# MCU.net
KiCad netlist of a schematic drawn in Altium Designer
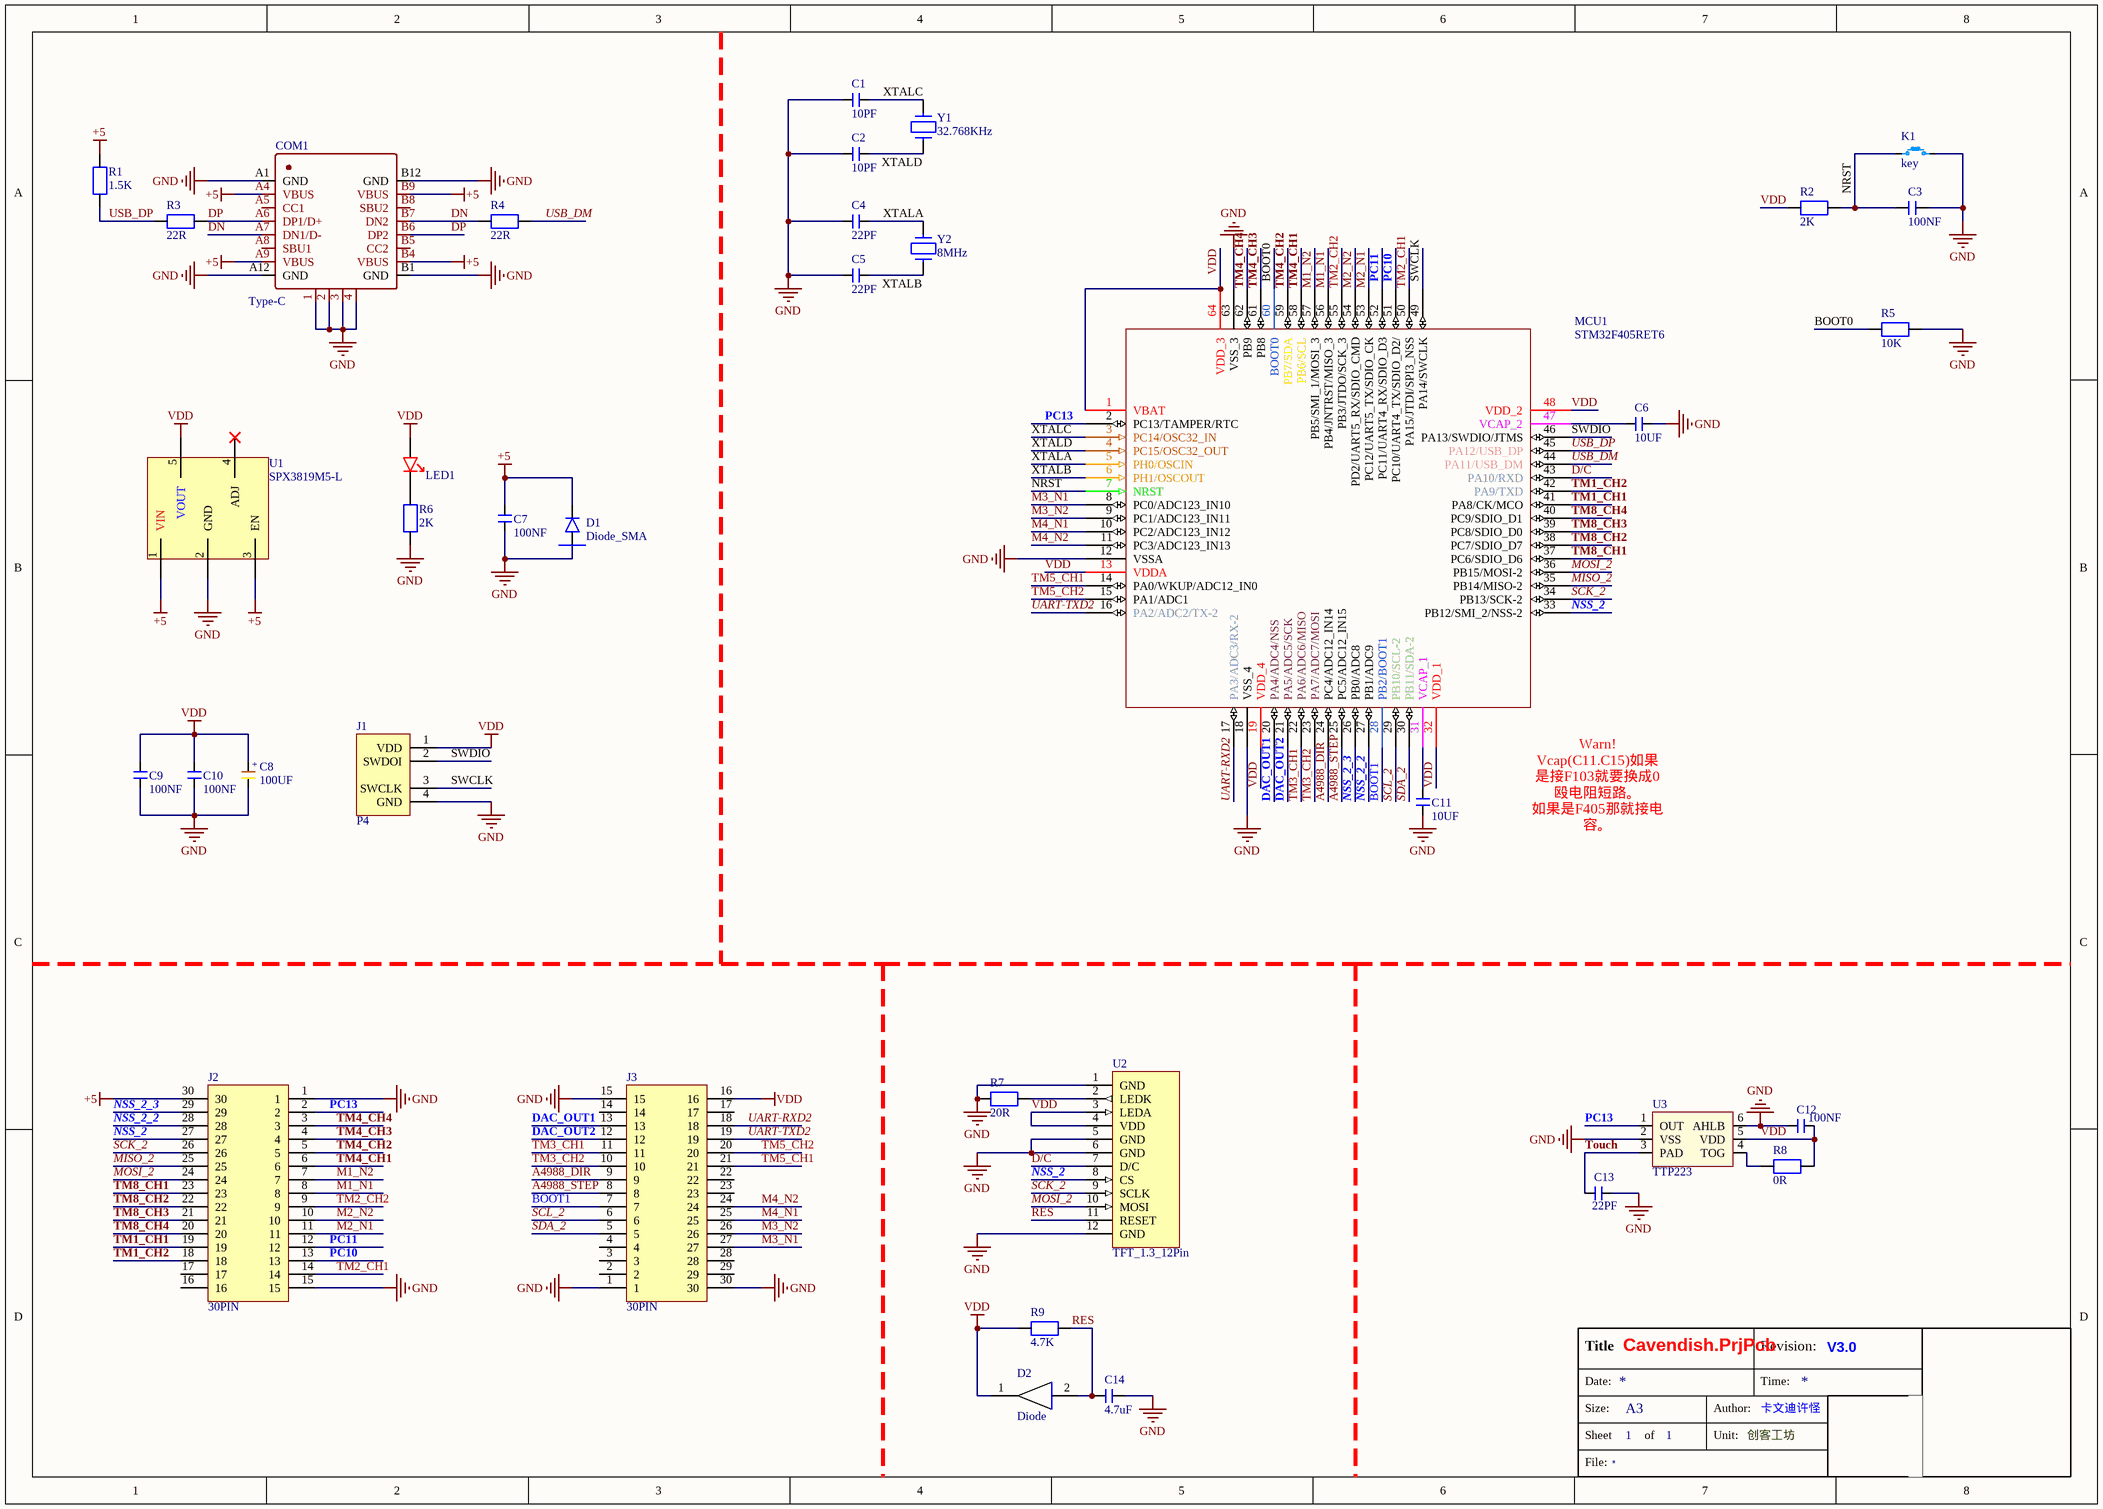
[diagram p0: MCU.SchDoc]

(export (version "E")
  (design (tool "Eeschema 10.0.6"))
  (components
    (comp (ref "C1")
      (value "10PF")
      (footprint "CAP_0603")
      (description "CAP  12~50V")
      (libsource (lib "User") (part "CAP"))
    )
    (comp (ref "C2")
      (value "10PF")
      (footprint "CAP_0603")
      (description "CAP  12~50V")
      (libsource (lib "User") (part "CAP"))
    )
    (comp (ref "C3")
      (value "100NF")
      (footprint "CAP_0603")
      (description "CAP")
      (libsource (lib "Schlib1") (part "CAP_SDM"))
    )
    (comp (ref "C4")
      (value "22PF")
      (footprint "CAP_0603")
      (description "CAP  12~50V")
      (libsource (lib "User") (part "CAP"))
    )
    (comp (ref "C5")
      (value "22PF")
      (footprint "CAP_0603")
      (description "CAP  12~50V")
      (libsource (lib "User") (part "CAP"))
    )
    (comp (ref "C6")
      (value "10UF")
      (footprint "CAP_0603")
      (description "CAP  12~50V")
      (libsource (lib "User") (part "CAP"))
    )
    (comp (ref "C7")
      (value "100NF")
      (footprint "CAP_0603")
      (description "CAP  12~50V")
      (libsource (lib "User") (part "CAP"))
    )
    (comp (ref "C8")
      (value "100UF")
      (footprint "CAP_3528_B")
      (description "CAP  6~12V  钽电容")
      (libsource (lib "User") (part "CAP_TA"))
    )
    (comp (ref "C9")
      (value "100NF")
      (footprint "CAP_0603")
      (description "CAP  12~50V")
      (libsource (lib "User") (part "CAP"))
    )
    (comp (ref "C10")
      (value "100NF")
      (footprint "CAP_0603")
      (description "CAP  12~50V")
      (libsource (lib "User") (part "CAP"))
    )
    (comp (ref "C11")
      (value "10UF")
      (footprint "CAP_0603")
      (description "CAP  12~50V")
      (libsource (lib "User") (part "CAP"))
    )
    (comp (ref "C12")
      (value "100NF")
      (footprint "CAP_0603")
      (description "CAP  12~50V")
      (libsource (lib "User") (part "CAP"))
    )
    (comp (ref "C13")
      (value "22PF")
      (footprint "CAP_0603")
      (description "CAP  12~50V")
      (libsource (lib "User") (part "CAP"))
    )
    (comp (ref "C14")
      (value "4.7uF")
      (footprint "CAP_0603")
      (description "CAP")
      (libsource (lib "Schlib1") (part "CAP_SDM"))
    )
    (comp (ref "COM1")
      (value "Type-C")
      (footprint "USB-tYPE_C_C")
      (description "USB")
      (libsource (lib "User") (part "USB-type_c"))
    )
    (comp (ref "D1")
      (value "Diode_SMA")
      (footprint "DIODE_SOD123")
      (description "Diode_肖特基")
      (libsource (lib "User") (part "Diode-SM"))
    )
    (comp (ref "D2")
      (value "Diode")
      (footprint "SOD123")
      (description "开关二极管")
      (libsource (lib "Schlib1") (part "Diode-SOD"))
    )
    (comp (ref "J1") (value "P4") (footprint "XH2.54-WS-4P") (libsource (lib "User") (part "SWD")))
    (comp (ref "J2")
      (value "30PIN")
      (footprint "BTB_Double_30Pin_Up")
      (libsource (lib "") (part "BTB_DOUBLE_30PIN_1"))
    )
    (comp (ref "J3")
      (value "30PIN")
      (footprint "BTB_Double_30Pin_Up")
      (libsource (lib "User") (part "BTB_DOUBLE_30PIN"))
    )
    (comp (ref "K1")
      (value "key")
      (footprint "KEY-A")
      (description "Key")
      (libsource (lib "Schlib1") (part "key"))
    )
    (comp (ref "LED1")
      (value "LED_R/G/B/Y")
      (footprint "LED_0603_R")
      (description "LED")
      (libsource (lib "User") (part "LED"))
    )
    (comp (ref "MCU1")
      (value "STM32F405RET6")
      (footprint "LQFP_64_10X10")
      (description "MCU")
      (libsource (lib "User") (part "STM32f4_R"))
    )
    (comp (ref "R1")
      (value "1.5K")
      (footprint "RESC_0603_2")
      (description "RES 贴片")
      (libsource (lib "User") (part "RES_S"))
    )
    (comp (ref "R2")
      (value "2K")
      (footprint "RESC_0603_2")
      (description "RES 贴片")
      (libsource (lib "User") (part "RES_S"))
    )
    (comp (ref "R3")
      (value "22R")
      (footprint "RESC_0603_2")
      (description "RES 贴片")
      (libsource (lib "User") (part "RES_S"))
    )
    (comp (ref "R4")
      (value "22R")
      (footprint "RESC_0603_2")
      (description "RES 贴片")
      (libsource (lib "User") (part "RES_S"))
    )
    (comp (ref "R5")
      (value "10K")
      (footprint "RESC_0603_2")
      (description "RES 贴片")
      (libsource (lib "User") (part "RES_S"))
    )
    (comp (ref "R6")
      (value "2K")
      (footprint "RESC_0603_2")
      (description "RES 贴片")
      (libsource (lib "User") (part "RES_S"))
    )
    (comp (ref "R7")
      (value "20R")
      (footprint "RESC_0603_2")
      (description "RES 贴片")
      (libsource (lib "User") (part "RES_S"))
    )
    (comp (ref "R8")
      (value "0R")
      (footprint "RESC_0603_2")
      (description "RES 贴片")
      (libsource (lib "User") (part "RES_S"))
    )
    (comp (ref "R9")
      (value "4.7K")
      (footprint "RESC_0603_2")
      (description "RES 贴片")
      (libsource (lib "User") (part "RES_S"))
    )
    (comp (ref "U1")
      (value "SPX3819M5-L")
      (footprint "SOT23_5")
      (description "DC-DC   3.3V  500ma")
      (libsource (lib "Schlib1") (part "SPX3819M5-L"))
    )
    (comp (ref "U2")
      (value "TFT_1.3_12Pin")
      (footprint "LCD_1.3B")
      (description "ST7789V-SPI")
      (libsource (lib "User") (part "LCD_1.3   T"))
    )
    (comp (ref "U3")
      (value "TTP223")
      (footprint "SOT-23-6")
      (description "触摸芯片")
      (libsource (lib "User") (part "TTP223"))
    )
    (comp (ref "Y1")
      (value "32.768KHz")
      (footprint "XTAL_SMD_3215")
      (description "CRYSTAL")
      (libsource (lib "Schlib1") (part "XTAL"))
    )
    (comp (ref "Y2")
      (value "8MHz")
      (footprint "XTAL_3225")
      (description "CRYSTAL")
      (libsource (lib "Schlib1") (part "XTAL"))
    )
  )
  (nets
    (net (code "1") (name "+5") (class "Default")
      (node (ref "C7") (pin "2") (pinfunction "0_2") (pintype "passive"))
      (node (ref "COM1") (pin "A4") (pinfunction "VBUS_A4") (pintype "passive"))
      (node (ref "COM1") (pin "A9") (pinfunction "VBUS_A9") (pintype "passive"))
      (node (ref "COM1") (pin "B4") (pinfunction "VBUS_B4") (pintype "passive"))
      (node (ref "COM1") (pin "B9") (pinfunction "VBUS_B9") (pintype "passive"))
      (node (ref "D1") (pin "2") (pinfunction "N_2") (pintype "passive"))
      (node (ref "J2") (pin "30") (pinfunction "30_30") (pintype "passive"))
      (node (ref "R1") (pin "1") (pinfunction "1_1") (pintype "passive"))
      (node (ref "U1") (pin "1") (pinfunction "VIN_1") (pintype "passive"))
      (node (ref "U1") (pin "3") (pinfunction "EN_3") (pintype "passive"))
    )
    (net (code "2") (name "/A4988_DIR") (class "Default")
      (node (ref "J3") (pin "9") (pinfunction "9_9") (pintype "passive"))
      (node (ref "MCU1") (pin "24") (pinfunction "PC4/ADC12_IN14_24") (pintype "bidirectional"))
    )
    (net (code "3") (name "/A4988_STEP") (class "Default")
      (node (ref "J3") (pin "8") (pinfunction "8_8") (pintype "passive"))
      (node (ref "MCU1") (pin "25") (pinfunction "PC5/ADC12_IN15_25") (pintype "bidirectional"))
    )
    (net (code "4") (name "/BOOT0") (class "Default")
      (node (ref "MCU1") (pin "60") (pinfunction "BOOT0_60") (pintype "passive"))
      (node (ref "R5") (pin "1") (pinfunction "1_1") (pintype "passive"))
    )
    (net (code "5") (name "/BOOT1") (class "Default")
      (node (ref "J3") (pin "7") (pinfunction "7_7") (pintype "passive"))
      (node (ref "MCU1") (pin "28") (pinfunction "PB2/BOOT1_28") (pintype "passive"))
    )
    (net (code "6") (name "/DAC_OUT1") (class "Default")
      (node (ref "J3") (pin "13") (pinfunction "13_13") (pintype "passive"))
      (node (ref "MCU1") (pin "20") (pinfunction "PA4/ADC4/NSS_20") (pintype "bidirectional"))
    )
    (net (code "7") (name "/DAC_OUT2") (class "Default")
      (node (ref "J3") (pin "12") (pinfunction "12_12") (pintype "passive"))
      (node (ref "MCU1") (pin "21") (pinfunction "PA5/ADC5/SCK_21") (pintype "bidirectional"))
    )
    (net (code "8") (name "/DN") (class "Default")
      (node (ref "COM1") (pin "A7") (pinfunction "DN1/D-_A7") (pintype "passive"))
      (node (ref "COM1") (pin "B7") (pinfunction "DN2_B7") (pintype "passive"))
      (node (ref "R4") (pin "1") (pinfunction "1_1") (pintype "passive"))
    )
    (net (code "9") (name "/DP") (class "Default")
      (node (ref "COM1") (pin "A6") (pinfunction "DP1/D+_A6") (pintype "passive"))
      (node (ref "COM1") (pin "B6") (pinfunction "DP2_B6") (pintype "passive"))
      (node (ref "R3") (pin "1") (pinfunction "1_1") (pintype "passive"))
    )
    (net (code "10") (name "/D{slash}C") (class "Default")
      (node (ref "MCU1") (pin "43") (pinfunction "PA10/RXD_43") (pintype "bidirectional"))
      (node (ref "U2") (pin "7") (pinfunction "D/C_7") (pintype "passive"))
    )
    (net (code "11") (name "/M1_N1") (class "Default")
      (node (ref "J2") (pin "8") (pinfunction "8_8") (pintype "passive"))
      (node (ref "MCU1") (pin "56") (pinfunction "PB4/JNTRST/MISO_3_56") (pintype "bidirectional"))
    )
    (net (code "12") (name "/M1_N2") (class "Default")
      (node (ref "J2") (pin "7") (pinfunction "7_7") (pintype "passive"))
      (node (ref "MCU1") (pin "57") (pinfunction "PB5/SMI_1/MOSI_3_57") (pintype "bidirectional"))
    )
    (net (code "13") (name "/M2_N1") (class "Default")
      (node (ref "J2") (pin "11") (pinfunction "11_11") (pintype "passive"))
      (node (ref "MCU1") (pin "53") (pinfunction "PC12/UART5_TX/SDIO_CK_53") (pintype "bidirectional"))
    )
    (net (code "14") (name "/M2_N2") (class "Default")
      (node (ref "J2") (pin "10") (pinfunction "10_10") (pintype "passive"))
      (node (ref "MCU1") (pin "54") (pinfunction "PD2/UART5_RX/SDIO_CMD_54") (pintype "bidirectional"))
    )
    (net (code "15") (name "/M3_N1") (class "Default")
      (node (ref "J3") (pin "27") (pinfunction "27_27") (pintype "passive"))
      (node (ref "MCU1") (pin "8") (pinfunction "PC0/ADC123_IN10_8") (pintype "bidirectional"))
    )
    (net (code "16") (name "/M3_N2") (class "Default")
      (node (ref "J3") (pin "26") (pinfunction "26_26") (pintype "passive"))
      (node (ref "MCU1") (pin "9") (pinfunction "PC1/ADC123_IN11_9") (pintype "bidirectional"))
    )
    (net (code "17") (name "/M4_N1") (class "Default")
      (node (ref "J3") (pin "25") (pinfunction "25_25") (pintype "passive"))
      (node (ref "MCU1") (pin "10") (pinfunction "PC2/ADC123_IN12_10") (pintype "bidirectional"))
    )
    (net (code "18") (name "/M4_N2") (class "Default")
      (node (ref "J3") (pin "24") (pinfunction "24_24") (pintype "passive"))
      (node (ref "MCU1") (pin "11") (pinfunction "PC3/ADC123_IN13_11") (pintype "bidirectional"))
    )
    (net (code "19") (name "/MISO_2") (class "Default")
      (node (ref "J2") (pin "25") (pinfunction "25_25") (pintype "passive"))
      (node (ref "MCU1") (pin "35") (pinfunction "PB14/MISO-2_35") (pintype "bidirectional"))
    )
    (net (code "20") (name "/MOSI_2") (class "Default")
      (node (ref "J2") (pin "24") (pinfunction "24_24") (pintype "passive"))
      (node (ref "MCU1") (pin "36") (pinfunction "PB15/MOSI-2_36") (pintype "bidirectional"))
      (node (ref "U2") (pin "10") (pinfunction "MOSI_10") (pintype "input"))
    )
    (net (code "21") (name "/NRST") (class "Default")
      (node (ref "C3") (pin "2") (pinfunction "0_2") (pintype "passive"))
      (node (ref "K1") (pin "2") (pintype "passive"))
      (node (ref "MCU1") (pin "7") (pinfunction "NRST_7") (pintype "input"))
      (node (ref "R2") (pin "2") (pinfunction "2_2") (pintype "passive"))
    )
    (net (code "22") (name "/NSS_2") (class "Default")
      (node (ref "J2") (pin "27") (pinfunction "27_27") (pintype "passive"))
      (node (ref "MCU1") (pin "33") (pinfunction "PB12/SMI_2/NSS-2_33") (pintype "bidirectional"))
      (node (ref "U2") (pin "8") (pinfunction "CS_8") (pintype "input"))
    )
    (net (code "23") (name "/NSS_2_2") (class "Default")
      (node (ref "J2") (pin "28") (pinfunction "28_28") (pintype "passive"))
      (node (ref "MCU1") (pin "27") (pinfunction "PB1/ADC9_27") (pintype "bidirectional"))
    )
    (net (code "24") (name "/NSS_2_3") (class "Default")
      (node (ref "J2") (pin "29") (pinfunction "29_29") (pintype "passive"))
      (node (ref "MCU1") (pin "26") (pinfunction "PB0/ADC8_26") (pintype "bidirectional"))
    )
    (net (code "25") (name "/PC10") (class "Default")
      (node (ref "J2") (pin "13") (pinfunction "13_13") (pintype "passive"))
      (node (ref "MCU1") (pin "51") (pinfunction "PC10/UART4_TX/SDIO_D2/_51") (pintype "bidirectional"))
    )
    (net (code "26") (name "/PC11") (class "Default")
      (node (ref "J2") (pin "12") (pinfunction "12_12") (pintype "passive"))
      (node (ref "MCU1") (pin "52") (pinfunction "PC11/UART4_RX/SDIO_D3_52") (pintype "bidirectional"))
    )
    (net (code "27") (name "/PC13") (class "Default")
      (node (ref "J2") (pin "2") (pinfunction "2_2") (pintype "passive"))
      (node (ref "MCU1") (pin "2") (pinfunction "PC13/TAMPER/RTC_2") (pintype "bidirectional"))
      (node (ref "U3") (pin "1") (pinfunction "OUT_1") (pintype "passive"))
    )
    (net (code "28") (name "/RES") (class "Default")
      (node (ref "C14") (pin "2") (pinfunction "0_2") (pintype "passive"))
      (node (ref "D2") (pin "2") (pinfunction "P_2") (pintype "passive"))
      (node (ref "R9") (pin "2") (pinfunction "2_2") (pintype "passive"))
      (node (ref "U2") (pin "11") (pinfunction "RESET_11") (pintype "passive"))
    )
    (net (code "29") (name "/SCK_2") (class "Default")
      (node (ref "J2") (pin "26") (pinfunction "26_26") (pintype "passive"))
      (node (ref "MCU1") (pin "34") (pinfunction "PB13/SCK-2_34") (pintype "bidirectional"))
      (node (ref "U2") (pin "9") (pinfunction "SCLK_9") (pintype "input"))
    )
    (net (code "30") (name "/SCL_2") (class "Default")
      (node (ref "J3") (pin "6") (pinfunction "6_6") (pintype "passive"))
      (node (ref "MCU1") (pin "29") (pinfunction "PB10/SCL-2_29") (pintype "bidirectional"))
    )
    (net (code "31") (name "/SDA_2") (class "Default")
      (node (ref "J3") (pin "5") (pinfunction "5_5") (pintype "passive"))
      (node (ref "MCU1") (pin "30") (pinfunction "PB11/SDA-2_30") (pintype "bidirectional"))
    )
    (net (code "32") (name "/SWCLK") (class "Default")
      (node (ref "J1") (pin "3") (pinfunction "SWCLK_3") (pintype "passive"))
      (node (ref "MCU1") (pin "49") (pinfunction "PA14/SWCLK_49") (pintype "bidirectional"))
    )
    (net (code "33") (name "/SWDIO") (class "Default")
      (node (ref "J1") (pin "2") (pinfunction "SWDOI_2") (pintype "passive"))
      (node (ref "MCU1") (pin "46") (pinfunction "PA13/SWDIO/JTMS_46") (pintype "bidirectional"))
    )
    (net (code "34") (name "/TM1_CH1") (class "Default")
      (node (ref "J2") (pin "19") (pinfunction "19_19") (pintype "passive"))
      (node (ref "MCU1") (pin "41") (pinfunction "PA8/CK/MCO_41") (pintype "bidirectional"))
    )
    (net (code "35") (name "/TM1_CH2") (class "Default")
      (node (ref "J2") (pin "18") (pinfunction "18_18") (pintype "passive"))
      (node (ref "MCU1") (pin "42") (pinfunction "PA9/TXD_42") (pintype "bidirectional"))
    )
    (net (code "36") (name "/TM2_CH1") (class "Default")
      (node (ref "J2") (pin "14") (pinfunction "14_14") (pintype "passive"))
      (node (ref "MCU1") (pin "50") (pinfunction "PA15/JTDI/SPI3_NSS_50") (pintype "bidirectional"))
    )
    (net (code "37") (name "/TM2_CH2") (class "Default")
      (node (ref "J2") (pin "9") (pinfunction "9_9") (pintype "passive"))
      (node (ref "MCU1") (pin "55") (pinfunction "PB3/JTDO/SCK_3_55") (pintype "bidirectional"))
    )
    (net (code "38") (name "/TM3_CH1") (class "Default")
      (node (ref "J3") (pin "11") (pinfunction "11_11") (pintype "passive"))
      (node (ref "MCU1") (pin "22") (pinfunction "PA6/ADC6/MISO_22") (pintype "bidirectional"))
    )
    (net (code "39") (name "/TM3_CH2") (class "Default")
      (node (ref "J3") (pin "10") (pinfunction "10_10") (pintype "passive"))
      (node (ref "MCU1") (pin "23") (pinfunction "PA7/ADC7/MOSI_23") (pintype "bidirectional"))
    )
    (net (code "40") (name "/TM4_CH1") (class "Default")
      (node (ref "J2") (pin "6") (pinfunction "6_6") (pintype "passive"))
      (node (ref "MCU1") (pin "58") (pinfunction "PB6/SCL_58") (pintype "bidirectional"))
    )
    (net (code "41") (name "/TM4_CH2") (class "Default")
      (node (ref "J2") (pin "5") (pinfunction "5_5") (pintype "passive"))
      (node (ref "MCU1") (pin "59") (pinfunction "PB7/SDA_59") (pintype "bidirectional"))
    )
    (net (code "42") (name "/TM4_CH3") (class "Default")
      (node (ref "J2") (pin "4") (pinfunction "4_4") (pintype "passive"))
      (node (ref "MCU1") (pin "61") (pinfunction "PB8_61") (pintype "bidirectional"))
    )
    (net (code "43") (name "/TM4_CH4") (class "Default")
      (node (ref "J2") (pin "3") (pinfunction "3_3") (pintype "passive"))
      (node (ref "MCU1") (pin "62") (pinfunction "PB9_62") (pintype "bidirectional"))
    )
    (net (code "44") (name "/TM5_CH1") (class "Default")
      (node (ref "J3") (pin "21") (pinfunction "21_21") (pintype "passive"))
      (node (ref "MCU1") (pin "14") (pinfunction "PA0/WKUP/ADC12_IN0_14") (pintype "bidirectional"))
    )
    (net (code "45") (name "/TM5_CH2") (class "Default")
      (node (ref "J3") (pin "20") (pinfunction "20_20") (pintype "passive"))
      (node (ref "MCU1") (pin "15") (pinfunction "PA1/ADC1_15") (pintype "bidirectional"))
    )
    (net (code "46") (name "/TM8_CH1") (class "Default")
      (node (ref "J2") (pin "23") (pinfunction "23_23") (pintype "passive"))
      (node (ref "MCU1") (pin "37") (pinfunction "PC6/SDIO_D6_37") (pintype "bidirectional"))
    )
    (net (code "47") (name "/TM8_CH2") (class "Default")
      (node (ref "J2") (pin "22") (pinfunction "22_22") (pintype "passive"))
      (node (ref "MCU1") (pin "38") (pinfunction "PC7/SDIO_D7_38") (pintype "bidirectional"))
    )
    (net (code "48") (name "/TM8_CH3") (class "Default")
      (node (ref "J2") (pin "21") (pinfunction "21_21") (pintype "passive"))
      (node (ref "MCU1") (pin "39") (pinfunction "PC8/SDIO_D0_39") (pintype "bidirectional"))
    )
    (net (code "49") (name "/TM8_CH4") (class "Default")
      (node (ref "J2") (pin "20") (pinfunction "20_20") (pintype "passive"))
      (node (ref "MCU1") (pin "40") (pinfunction "PC9/SDIO_D1_40") (pintype "bidirectional"))
    )
    (net (code "50") (name "/Touch") (class "Default")
      (node (ref "C13") (pin "1") (pinfunction "0_1") (pintype "passive"))
      (node (ref "U3") (pin "3") (pinfunction "PAD_3") (pintype "passive"))
    )
    (net (code "51") (name "/UART-RXD2") (class "Default")
      (node (ref "J3") (pin "18") (pinfunction "18_18") (pintype "passive"))
      (node (ref "MCU1") (pin "17") (pinfunction "PA3/ADC3/RX-2_17") (pintype "bidirectional"))
    )
    (net (code "52") (name "/UART-TXD2") (class "Default")
      (node (ref "J3") (pin "19") (pinfunction "19_19") (pintype "passive"))
      (node (ref "MCU1") (pin "16") (pinfunction "PA2/ADC2/TX-2_16") (pintype "bidirectional"))
    )
    (net (code "53") (name "/USB_DM") (class "Default")
      (node (ref "MCU1") (pin "44") (pinfunction "PA11/USB_DM_44") (pintype "bidirectional"))
      (node (ref "R4") (pin "2") (pinfunction "2_2") (pintype "passive"))
    )
    (net (code "54") (name "/USB_DP") (class "Default")
      (node (ref "MCU1") (pin "45") (pinfunction "PA12/USB_DP_45") (pintype "bidirectional"))
      (node (ref "R1") (pin "2") (pinfunction "2_2") (pintype "passive"))
      (node (ref "R3") (pin "2") (pinfunction "2_2") (pintype "passive"))
    )
    (net (code "55") (name "/XTALA") (class "Default")
      (node (ref "C4") (pin "1") (pinfunction "0_1") (pintype "passive"))
      (node (ref "MCU1") (pin "5") (pinfunction "PH0/OSCIN_5") (pintype "input"))
      (node (ref "Y2") (pin "2") (pinfunction "2_2") (pintype "passive"))
    )
    (net (code "56") (name "/XTALB") (class "Default")
      (node (ref "C5") (pin "1") (pinfunction "0_1") (pintype "passive"))
      (node (ref "MCU1") (pin "6") (pinfunction "PH1/OSCOUT_6") (pintype "input"))
      (node (ref "Y2") (pin "1") (pinfunction "1_1") (pintype "passive"))
    )
    (net (code "57") (name "/XTALC") (class "Default")
      (node (ref "C1") (pin "1") (pinfunction "0_1") (pintype "passive"))
      (node (ref "MCU1") (pin "3") (pinfunction "PC14/OSC32_IN_3") (pintype "input"))
      (node (ref "Y1") (pin "2") (pinfunction "2_2") (pintype "passive"))
    )
    (net (code "58") (name "/XTALD") (class "Default")
      (node (ref "C2") (pin "1") (pinfunction "0_1") (pintype "passive"))
      (node (ref "MCU1") (pin "4") (pinfunction "PC15/OSC32_OUT_4") (pintype "input"))
      (node (ref "Y1") (pin "1") (pinfunction "1_1") (pintype "passive"))
    )
    (net (code "59") (name "GND") (class "Default")
      (node (ref "C1") (pin "2") (pinfunction "0_2") (pintype "passive"))
      (node (ref "C10") (pin "1") (pinfunction "0_1") (pintype "passive"))
      (node (ref "C11") (pin "1") (pinfunction "0_1") (pintype "passive"))
      (node (ref "C12") (pin "1") (pinfunction "0_1") (pintype "passive"))
      (node (ref "C13") (pin "2") (pinfunction "0_2") (pintype "passive"))
      (node (ref "C14") (pin "1") (pinfunction "0_1") (pintype "passive"))
      (node (ref "C2") (pin "2") (pinfunction "0_2") (pintype "passive"))
      (node (ref "C3") (pin "1") (pinfunction "0_1") (pintype "passive"))
      (node (ref "C4") (pin "2") (pinfunction "0_2") (pintype "passive"))
      (node (ref "C5") (pin "2") (pinfunction "0_2") (pintype "passive"))
      (node (ref "C6") (pin "1") (pinfunction "0_1") (pintype "passive"))
      (node (ref "C7") (pin "1") (pinfunction "0_1") (pintype "passive"))
      (node (ref "C8") (pin "2") (pinfunction "0_2") (pintype "passive"))
      (node (ref "C9") (pin "1") (pinfunction "0_1") (pintype "passive"))
      (node (ref "COM1") (pin "1") (pinfunction "1_1") (pintype "passive"))
      (node (ref "COM1") (pin "2") (pinfunction "2_2") (pintype "passive"))
      (node (ref "COM1") (pin "3") (pinfunction "3_3") (pintype "passive"))
      (node (ref "COM1") (pin "4") (pinfunction "4_4") (pintype "passive"))
      (node (ref "COM1") (pin "A1") (pinfunction "GND_A1") (pintype "passive"))
      (node (ref "COM1") (pin "A12") (pinfunction "GND_A12") (pintype "passive"))
      (node (ref "COM1") (pin "B1") (pinfunction "GND_B1") (pintype "passive"))
      (node (ref "COM1") (pin "B12") (pinfunction "GND_B12") (pintype "passive"))
      (node (ref "D1") (pin "1") (pinfunction "P_1") (pintype "passive"))
      (node (ref "J1") (pin "4") (pinfunction "GND_4") (pintype "passive"))
      (node (ref "J2") (pin "1") (pinfunction "1_1") (pintype "passive"))
      (node (ref "J2") (pin "15") (pinfunction "15_15") (pintype "passive"))
      (node (ref "J3") (pin "1") (pinfunction "1_1") (pintype "passive"))
      (node (ref "J3") (pin "15") (pinfunction "15_15") (pintype "passive"))
      (node (ref "J3") (pin "30") (pinfunction "30_30") (pintype "passive"))
      (node (ref "K1") (pin "1") (pintype "passive"))
      (node (ref "MCU1") (pin "12") (pinfunction "VSSA_12") (pintype "power_in"))
      (node (ref "MCU1") (pin "18") (pinfunction "VSS_4_18") (pintype "power_in"))
      (node (ref "MCU1") (pin "63") (pinfunction "VSS_3_63") (pintype "power_in"))
      (node (ref "R5") (pin "2") (pinfunction "2_2") (pintype "passive"))
      (node (ref "R6") (pin "2") (pinfunction "2_2") (pintype "passive"))
      (node (ref "R7") (pin "1") (pinfunction "1_1") (pintype "passive"))
      (node (ref "U1") (pin "2") (pinfunction "GND_2") (pintype "passive"))
      (node (ref "U2") (pin "1") (pinfunction "GND_1") (pintype "passive"))
      (node (ref "U2") (pin "12") (pinfunction "GND_12") (pintype "passive"))
      (node (ref "U2") (pin "5") (pinfunction "GND_5") (pintype "passive"))
      (node (ref "U2") (pin "6") (pinfunction "GND_6") (pintype "passive"))
      (node (ref "U3") (pin "2") (pinfunction "VSS_2") (pintype "passive"))
      (node (ref "U3") (pin "6") (pinfunction "AHLB_6") (pintype "passive"))
    )
    (net (code "60") (name "Net-(LED1--)") (class "Default")
      (node (ref "LED1") (pin "1") (pinfunction "-_1") (pintype "passive"))
      (node (ref "R6") (pin "1") (pinfunction "1_1") (pintype "passive"))
    )
    (net (code "61") (name "Net-(MCU1-VCAP_1)") (class "Default")
      (node (ref "C11") (pin "2") (pinfunction "0_2") (pintype "passive"))
      (node (ref "MCU1") (pin "31") (pinfunction "VCAP_1_31") (pintype "passive"))
    )
    (net (code "62") (name "Net-(MCU1-VCAP_2)") (class "Default")
      (node (ref "C6") (pin "2") (pinfunction "0_2") (pintype "passive"))
      (node (ref "MCU1") (pin "47") (pinfunction "VCAP_2_47") (pintype "passive"))
    )
    (net (code "63") (name "Net-(U2-LEDK)") (class "Default")
      (node (ref "R7") (pin "2") (pinfunction "2_2") (pintype "passive"))
      (node (ref "U2") (pin "2") (pinfunction "LEDK_2") (pintype "output"))
    )
    (net (code "64") (name "Net-(U3-TOG)") (class "Default")
      (node (ref "R8") (pin "1") (pinfunction "1_1") (pintype "passive"))
      (node (ref "U3") (pin "4") (pinfunction "TOG_4") (pintype "passive"))
    )
    (net (code "65") (name "VDD") (class "Default")
      (node (ref "C10") (pin "2") (pinfunction "0_2") (pintype "passive"))
      (node (ref "C12") (pin "2") (pinfunction "0_2") (pintype "passive"))
      (node (ref "C8") (pin "1") (pinfunction "0_1") (pintype "passive"))
      (node (ref "C9") (pin "2") (pinfunction "0_2") (pintype "passive"))
      (node (ref "D2") (pin "1") (pinfunction "N_1") (pintype "passive"))
      (node (ref "J1") (pin "1") (pinfunction "VDD_1") (pintype "passive"))
      (node (ref "J3") (pin "16") (pinfunction "16_16") (pintype "passive"))
      (node (ref "LED1") (pin "2") (pinfunction "+_2") (pintype "passive"))
      (node (ref "MCU1") (pin "1") (pinfunction "VBAT_1") (pintype "power_in"))
      (node (ref "MCU1") (pin "13") (pinfunction "VDDA_13") (pintype "power_in"))
      (node (ref "MCU1") (pin "19") (pinfunction "VDD_4_19") (pintype "power_in"))
      (node (ref "MCU1") (pin "32") (pinfunction "VDD_1_32") (pintype "power_in"))
      (node (ref "MCU1") (pin "48") (pinfunction "VDD_2_48") (pintype "power_in"))
      (node (ref "MCU1") (pin "64") (pinfunction "VDD_3_64") (pintype "power_in"))
      (node (ref "R2") (pin "1") (pinfunction "1_1") (pintype "passive"))
      (node (ref "R8") (pin "2") (pinfunction "2_2") (pintype "passive"))
      (node (ref "R9") (pin "1") (pinfunction "1_1") (pintype "passive"))
      (node (ref "U1") (pin "5") (pinfunction "VOUT_5") (pintype "passive"))
      (node (ref "U2") (pin "3") (pinfunction "LEDA_3") (pintype "input"))
      (node (ref "U2") (pin "4") (pinfunction "VDD_4") (pintype "passive"))
      (node (ref "U3") (pin "5") (pinfunction "VDD_5") (pintype "passive"))
    )
    (net (code "66") (name "unconnected-(COM1-CC1-PadA5)") (class "Default")
      (node (ref "COM1") (pin "A5") (pinfunction "CC1_A5") (pintype "passive"))
    )
    (net (code "67") (name "unconnected-(COM1-CC2-PadB5)") (class "Default")
      (node (ref "COM1") (pin "B5") (pinfunction "CC2_B5") (pintype "passive"))
    )
    (net (code "68") (name "unconnected-(COM1-SBU1-PadA8)") (class "Default")
      (node (ref "COM1") (pin "A8") (pinfunction "SBU1_A8") (pintype "passive"))
    )
    (net (code "69") (name "unconnected-(COM1-SBU2-PadB8)") (class "Default")
      (node (ref "COM1") (pin "B8") (pinfunction "SBU2_B8") (pintype "passive"))
    )
    (net (code "70") (name "unconnected-(J2-Pad16)") (class "Default")
      (node (ref "J2") (pin "16") (pinfunction "16_16") (pintype "passive"))
    )
    (net (code "71") (name "unconnected-(J2-Pad17)") (class "Default")
      (node (ref "J2") (pin "17") (pinfunction "17_17") (pintype "passive"))
    )
    (net (code "72") (name "unconnected-(J3-Pad2)") (class "Default")
      (node (ref "J3") (pin "2") (pinfunction "2_2") (pintype "passive"))
    )
    (net (code "73") (name "unconnected-(J3-Pad3)") (class "Default")
      (node (ref "J3") (pin "3") (pinfunction "3_3") (pintype "passive"))
    )
    (net (code "74") (name "unconnected-(J3-Pad4)") (class "Default")
      (node (ref "J3") (pin "4") (pinfunction "4_4") (pintype "passive"))
    )
    (net (code "75") (name "unconnected-(J3-Pad14)") (class "Default")
      (node (ref "J3") (pin "14") (pinfunction "14_14") (pintype "passive"))
    )
    (net (code "76") (name "unconnected-(J3-Pad17)") (class "Default")
      (node (ref "J3") (pin "17") (pinfunction "17_17") (pintype "passive"))
    )
    (net (code "77") (name "unconnected-(J3-Pad22)") (class "Default")
      (node (ref "J3") (pin "22") (pinfunction "22_22") (pintype "passive"))
    )
    (net (code "78") (name "unconnected-(J3-Pad23)") (class "Default")
      (node (ref "J3") (pin "23") (pinfunction "23_23") (pintype "passive"))
    )
    (net (code "79") (name "unconnected-(J3-Pad28)") (class "Default")
      (node (ref "J3") (pin "28") (pinfunction "28_28") (pintype "passive"))
    )
    (net (code "80") (name "unconnected-(J3-Pad29)") (class "Default")
      (node (ref "J3") (pin "29") (pinfunction "29_29") (pintype "passive"))
    )
    (net (code "81") (name "unconnected-(U1-ADJ-Pad4)") (class "Default")
      (node (ref "U1") (pin "4") (pinfunction "ADJ_4") (pintype "passive+no_connect"))
    )
  )
)
